# soar_demise.net
KiCad netlist of a schematic drawn in EAGLE
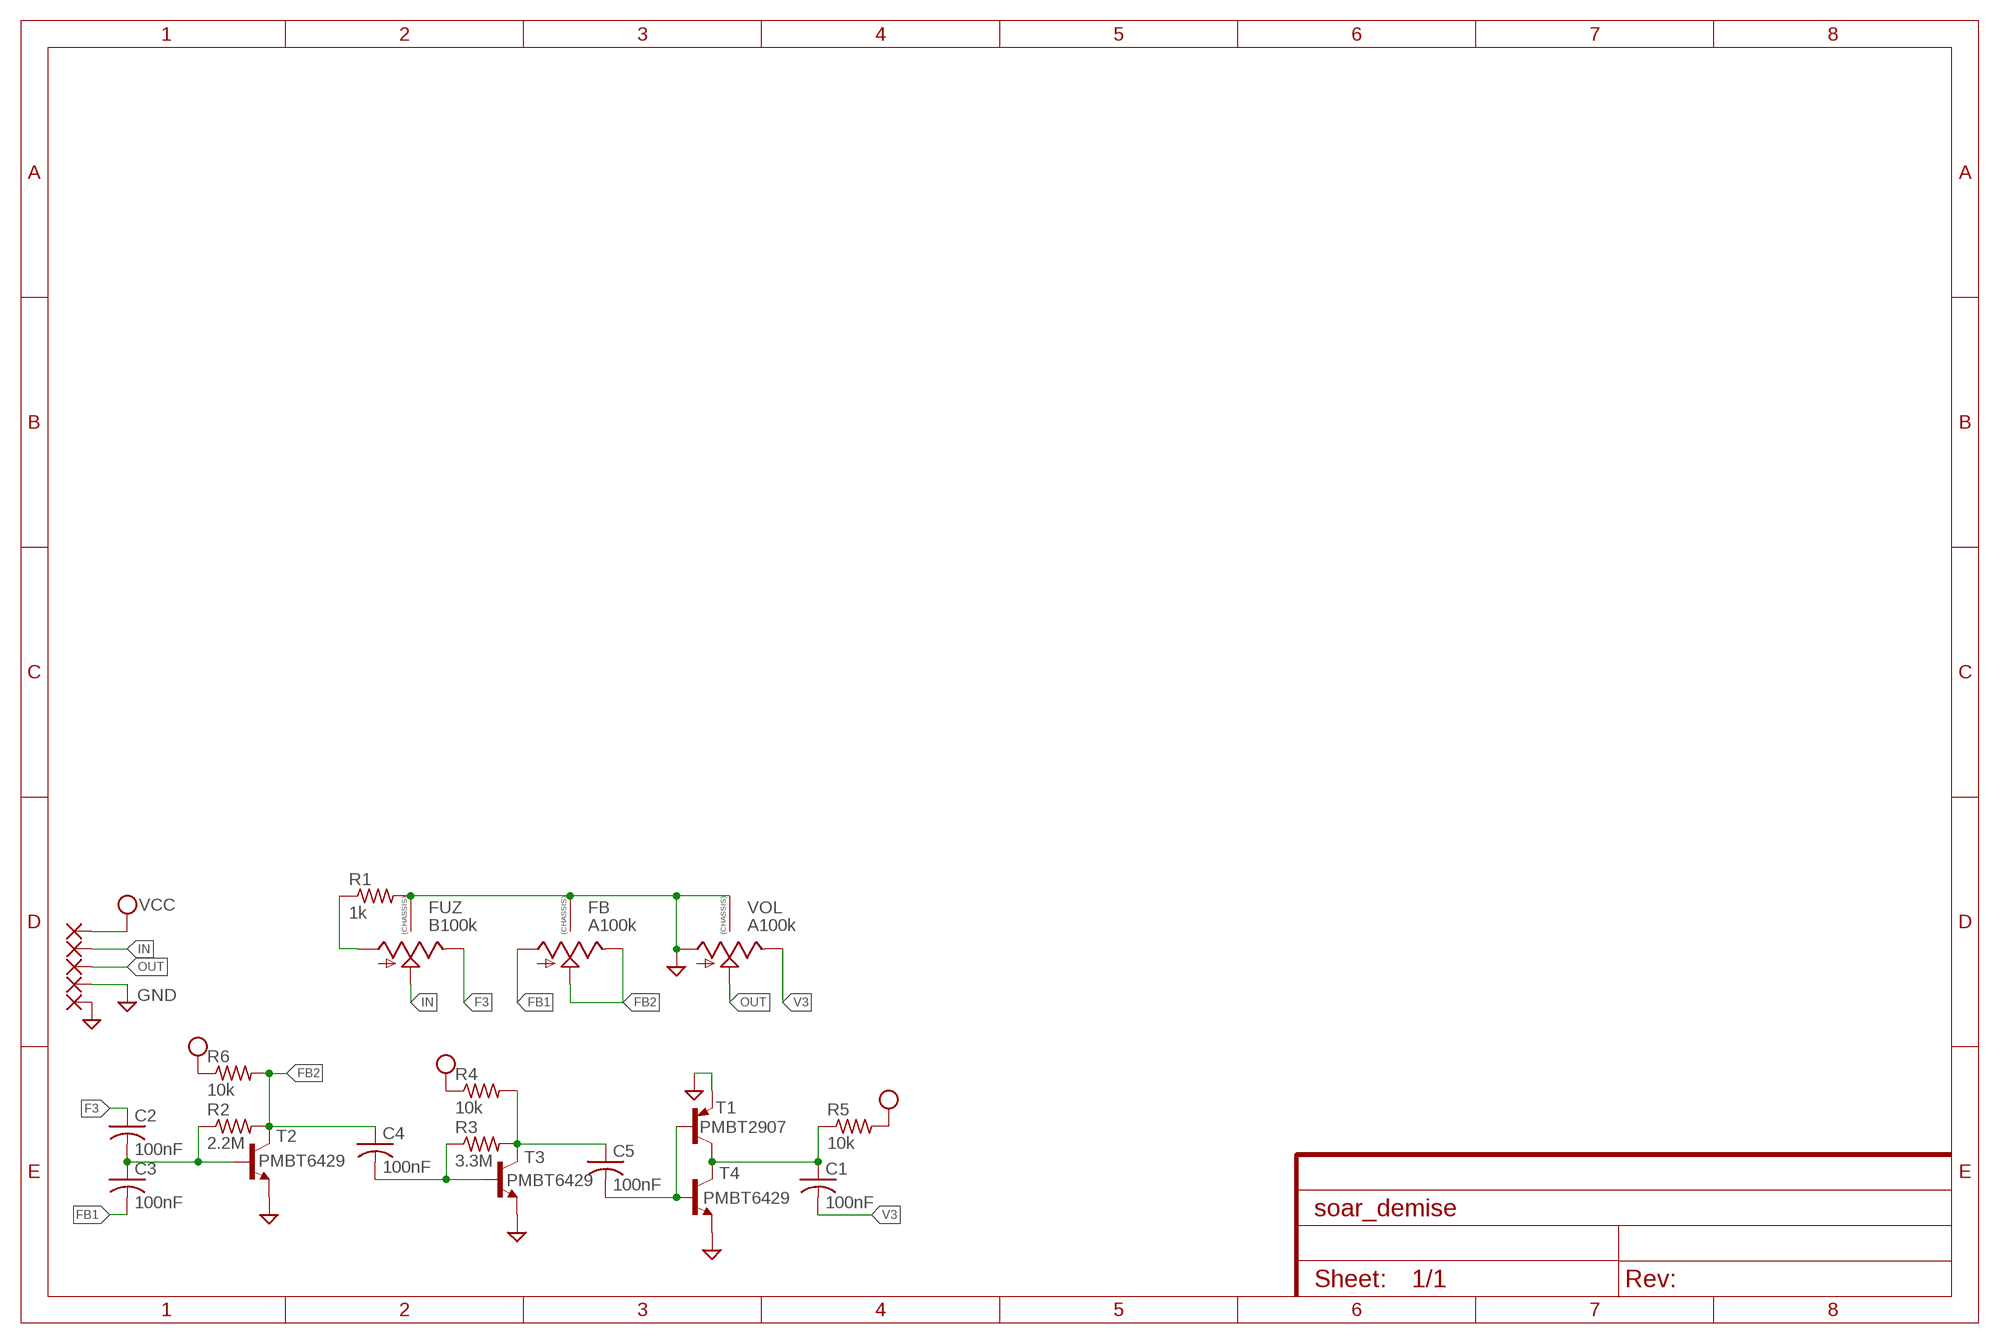
[diagram p0: schematic, sheet 1]

(export (version "E")
  (design (tool "Eeschema 10.0.6"))
  (components
    (comp (ref "C1")
      (value "100nF")
      (footprint "eagle-import:C0805")
      (libsource (lib "eagle-import") (part "C-USC0805"))
    )
    (comp (ref "C2")
      (value "100nF")
      (footprint "eagle-import:C0805")
      (libsource (lib "eagle-import") (part "C-USC0805"))
    )
    (comp (ref "C3")
      (value "100nF")
      (footprint "eagle-import:C0805")
      (libsource (lib "eagle-import") (part "C-USC0805"))
    )
    (comp (ref "C4")
      (value "100nF")
      (footprint "eagle-import:C0805")
      (libsource (lib "eagle-import") (part "C-USC0805"))
    )
    (comp (ref "C5")
      (value "100nF")
      (footprint "eagle-import:C0805")
      (libsource (lib "eagle-import") (part "C-USC0805"))
    )
    (comp (ref "FB")
      (value "A100k")
      (footprint "eagle-import:9MM_SNAP-IN_POT")
      (libsource (lib "eagle-import") (part "9MM_SNAP-IN_POT_CHASSIS"))
    )
    (comp (ref "FUZ")
      (value "B100k")
      (footprint "eagle-import:9MM_SNAP-IN_POT")
      (libsource (lib "eagle-import") (part "9MM_SNAP-IN_POT_CHASSIS"))
    )
    (comp (ref "PAD1")
      (value "1,6/0,8")
      (footprint "eagle-import:1,6_0,8")
      (libsource (lib "eagle-import") (part "1,6/0,8"))
    )
    (comp (ref "PAD2")
      (value "1,6/0,8")
      (footprint "eagle-import:1,6_0,8")
      (libsource (lib "eagle-import") (part "1,6/0,8"))
    )
    (comp (ref "PAD3")
      (value "1,6/0,8")
      (footprint "eagle-import:1,6_0,8")
      (libsource (lib "eagle-import") (part "1,6/0,8"))
    )
    (comp (ref "PAD4")
      (value "1,6/0,8")
      (footprint "eagle-import:1,6_0,8")
      (libsource (lib "eagle-import") (part "1,6/0,8"))
    )
    (comp (ref "PAD5")
      (value "1,6/0,8")
      (footprint "eagle-import:1,6_0,8")
      (libsource (lib "eagle-import") (part "1,6/0,8"))
    )
    (comp (ref "R1")
      (value "1k")
      (footprint "eagle-import:R0805")
      (libsource (lib "eagle-import") (part "R-US_R0805"))
    )
    (comp (ref "R2")
      (value "2.2M")
      (footprint "eagle-import:R0805")
      (libsource (lib "eagle-import") (part "R-US_R0805"))
    )
    (comp (ref "R3")
      (value "3.3M")
      (footprint "eagle-import:R0805")
      (libsource (lib "eagle-import") (part "R-US_R0805"))
    )
    (comp (ref "R4")
      (value "10k")
      (footprint "eagle-import:R0805")
      (libsource (lib "eagle-import") (part "R-US_R0805"))
    )
    (comp (ref "R5")
      (value "10k")
      (footprint "eagle-import:R0805")
      (libsource (lib "eagle-import") (part "R-US_R0805"))
    )
    (comp (ref "R6")
      (value "10k")
      (footprint "eagle-import:R0805")
      (libsource (lib "eagle-import") (part "R-US_R0805"))
    )
    (comp (ref "T1")
      (value "PMBT2907")
      (footprint "eagle-import:SOT23-BEC")
      (libsource (lib "eagle-import") (part "-PNP-SOT23-BECMMBT2907ALT1"))
    )
    (comp (ref "T2")
      (value "PMBT6429")
      (footprint "eagle-import:SOT23-BEC")
      (libsource (lib "eagle-import") (part "-NPN-SOT23-BECMMBT6429LT1"))
    )
    (comp (ref "T3")
      (value "PMBT6429")
      (footprint "eagle-import:SOT23-BEC")
      (libsource (lib "eagle-import") (part "-NPN-SOT23-BECMMBT6429LT1"))
    )
    (comp (ref "T4")
      (value "PMBT6429")
      (footprint "eagle-import:SOT23-BEC")
      (libsource (lib "eagle-import") (part "-NPN-SOT23-BECMMBT6429LT1"))
    )
    (comp (ref "VOL")
      (value "A100k")
      (footprint "eagle-import:9MM_SNAP-IN_POT")
      (libsource (lib "eagle-import") (part "9MM_SNAP-IN_POT_CHASSIS"))
    )
  )
  (nets
    (net (code "1") (name "F3") (class "Default")
      (node (ref "C2") (pin "1") (pinfunction "1_1") (pintype "passive"))
      (node (ref "FUZ") (pin "3") (pinfunction "E_3") (pintype "passive"))
    )
    (net (code "2") (name "FB1") (class "Default")
      (node (ref "C3") (pin "2") (pinfunction "2_2") (pintype "passive"))
      (node (ref "FB") (pin "1") (pinfunction "A_1") (pintype "passive"))
    )
    (net (code "3") (name "FB2") (class "Default")
      (node (ref "C4") (pin "1") (pinfunction "1_1") (pintype "passive"))
      (node (ref "FB") (pin "2") (pinfunction "S_2") (pintype "passive"))
      (node (ref "FB") (pin "3") (pinfunction "E_3") (pintype "passive"))
      (node (ref "R2") (pin "2") (pinfunction "2_2") (pintype "passive"))
      (node (ref "R6") (pin "2") (pinfunction "2_2") (pintype "passive"))
      (node (ref "T2") (pin "C") (pinfunction "C_C") (pintype "passive"))
    )
    (net (code "4") (name "GND") (class "Default")
      (node (ref "FB") (pin "CHASSIS1") (pinfunction "P$1_CHASSIS1") (pintype "passive"))
      (node (ref "FB") (pin "CHASSIS2") (pinfunction "P$1_CHASSIS2") (pintype "passive"))
      (node (ref "FUZ") (pin "CHASSIS1") (pinfunction "P$1_CHASSIS1") (pintype "passive"))
      (node (ref "FUZ") (pin "CHASSIS2") (pinfunction "P$1_CHASSIS2") (pintype "passive"))
      (node (ref "PAD4") (pin "1") (pinfunction "P_1") (pintype "passive"))
      (node (ref "PAD5") (pin "1") (pinfunction "P_1") (pintype "passive"))
      (node (ref "R1") (pin "2") (pinfunction "2_2") (pintype "passive"))
      (node (ref "T1") (pin "E") (pinfunction "E_E") (pintype "passive"))
      (node (ref "T2") (pin "E") (pinfunction "E_E") (pintype "passive"))
      (node (ref "T3") (pin "E") (pinfunction "E_E") (pintype "passive"))
      (node (ref "T4") (pin "E") (pinfunction "E_E") (pintype "passive"))
      (node (ref "VOL") (pin "1") (pinfunction "A_1") (pintype "passive"))
      (node (ref "VOL") (pin "CHASSIS1") (pinfunction "P$1_CHASSIS1") (pintype "passive"))
      (node (ref "VOL") (pin "CHASSIS2") (pinfunction "P$1_CHASSIS2") (pintype "passive"))
    )
    (net (code "5") (name "IN") (class "Default")
      (node (ref "FUZ") (pin "2") (pinfunction "S_2") (pintype "passive"))
      (node (ref "PAD2") (pin "1") (pinfunction "P_1") (pintype "passive"))
    )
    (net (code "6") (name "Net-(C1-Pad1)") (class "Default")
      (node (ref "C1") (pin "1") (pinfunction "1_1") (pintype "passive"))
      (node (ref "R5") (pin "1") (pinfunction "1_1") (pintype "passive"))
      (node (ref "T1") (pin "C") (pinfunction "C_C") (pintype "passive"))
      (node (ref "T4") (pin "C") (pinfunction "C_C") (pintype "passive"))
    )
    (net (code "7") (name "Net-(C2-Pad2)") (class "Default")
      (node (ref "C2") (pin "2") (pinfunction "2_2") (pintype "passive"))
      (node (ref "C3") (pin "1") (pinfunction "1_1") (pintype "passive"))
      (node (ref "R2") (pin "1") (pinfunction "1_1") (pintype "passive"))
      (node (ref "T2") (pin "B") (pinfunction "B_B") (pintype "passive"))
    )
    (net (code "8") (name "Net-(C4-Pad2)") (class "Default")
      (node (ref "C4") (pin "2") (pinfunction "2_2") (pintype "passive"))
      (node (ref "R3") (pin "1") (pinfunction "1_1") (pintype "passive"))
      (node (ref "T3") (pin "B") (pinfunction "B_B") (pintype "passive"))
    )
    (net (code "9") (name "Net-(C5-Pad1)") (class "Default")
      (node (ref "C5") (pin "1") (pinfunction "1_1") (pintype "passive"))
      (node (ref "R3") (pin "2") (pinfunction "2_2") (pintype "passive"))
      (node (ref "R4") (pin "2") (pinfunction "2_2") (pintype "passive"))
      (node (ref "T3") (pin "C") (pinfunction "C_C") (pintype "passive"))
    )
    (net (code "10") (name "Net-(C5-Pad2)") (class "Default")
      (node (ref "C5") (pin "2") (pinfunction "2_2") (pintype "passive"))
      (node (ref "T1") (pin "B") (pinfunction "B_B") (pintype "passive"))
      (node (ref "T4") (pin "B") (pinfunction "B_B") (pintype "passive"))
    )
    (net (code "11") (name "Net-(FUZ-A)") (class "Default")
      (node (ref "FUZ") (pin "1") (pinfunction "A_1") (pintype "passive"))
      (node (ref "R1") (pin "1") (pinfunction "1_1") (pintype "passive"))
    )
    (net (code "12") (name "OUT") (class "Default")
      (node (ref "PAD3") (pin "1") (pinfunction "P_1") (pintype "passive"))
      (node (ref "VOL") (pin "2") (pinfunction "S_2") (pintype "passive"))
    )
    (net (code "13") (name "V3") (class "Default")
      (node (ref "C1") (pin "2") (pinfunction "2_2") (pintype "passive"))
      (node (ref "VOL") (pin "3") (pinfunction "E_3") (pintype "passive"))
    )
    (net (code "14") (name "VCC") (class "Default")
      (node (ref "PAD1") (pin "1") (pinfunction "P_1") (pintype "passive"))
      (node (ref "R4") (pin "1") (pinfunction "1_1") (pintype "passive"))
      (node (ref "R5") (pin "2") (pinfunction "2_2") (pintype "passive"))
      (node (ref "R6") (pin "1") (pinfunction "1_1") (pintype "passive"))
    )
  )
)
